# Poke_2_3.net
KiCad netlist of a schematic drawn in EAGLE
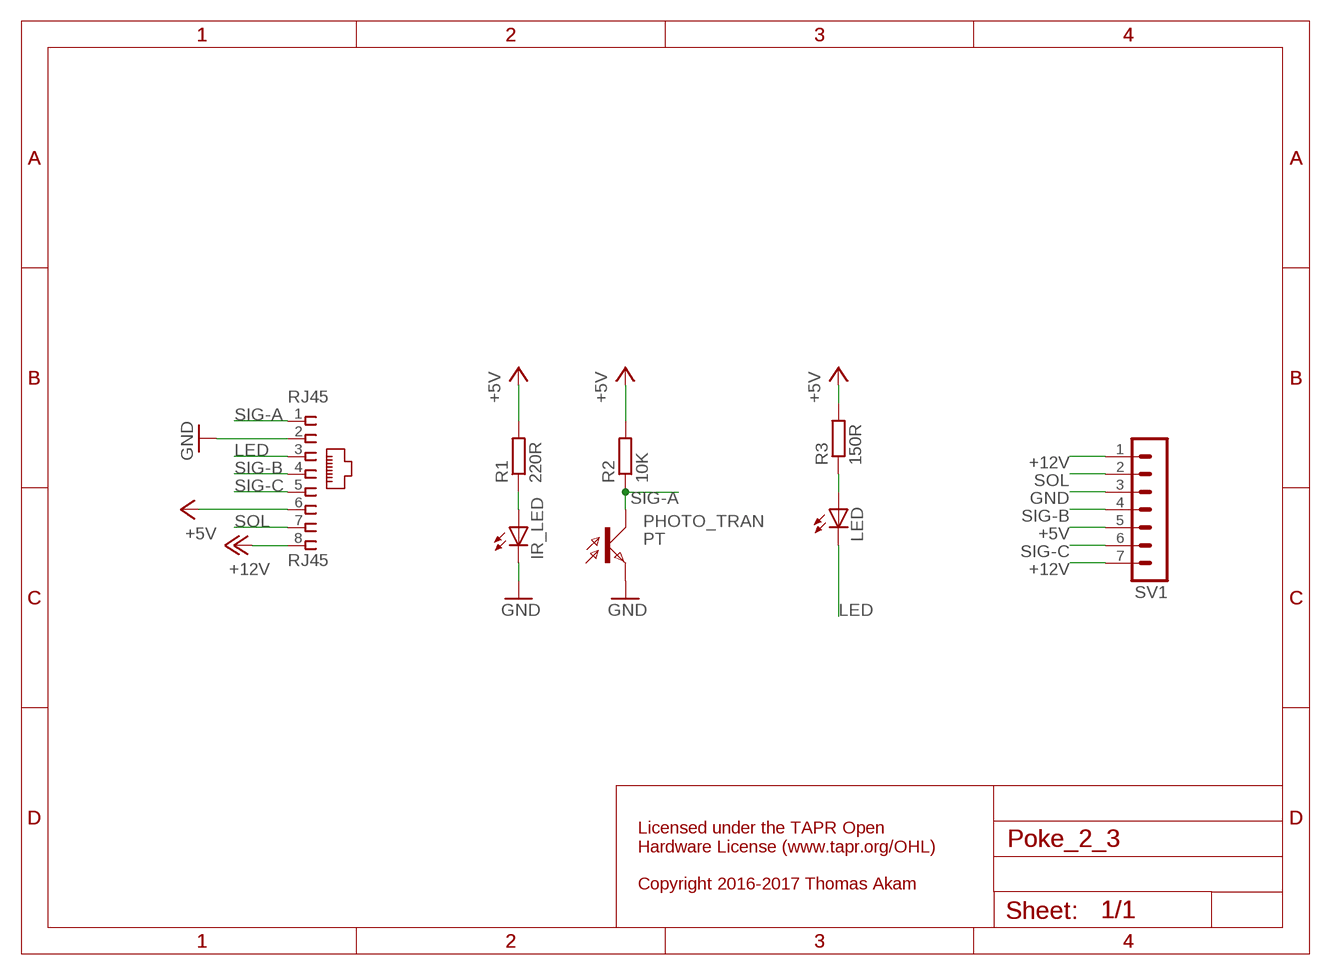
[diagram p0: schematic, sheet 1]

(export (version "E")
  (design (tool "Eeschema 10.0.6"))
  (components
    (comp (ref "IR_LED")
      (value "LEDIRL80A")
      (footprint "eagle-import:IRL80A")
      (libsource (lib "eagle-import") (part "LEDIRL80A"))
    )
    (comp (ref "LED")
      (value "LEDSML0805")
      (footprint "eagle-import:SML0805")
      (libsource (lib "eagle-import") (part "LEDSML0805"))
    )
    (comp (ref "PHOTO_TRAN")
      (value "PT")
      (footprint "eagle-import:LPT80A")
      (fields (field (name "OC_FARNELL") "unknown") (field (name "OC_NEWARK") "unknown"))
      (libsource (lib "eagle-import") (part "LPT80A"))
    )
    (comp (ref "R1")
      (value "220R")
      (footprint "eagle-import:R0805")
      (libsource (lib "eagle-import") (part "R-EU_R0805"))
    )
    (comp (ref "R2")
      (value "10K")
      (footprint "eagle-import:M0805")
      (libsource (lib "eagle-import") (part "R-EU_M0805"))
    )
    (comp (ref "R3")
      (value "150R")
      (footprint "eagle-import:M0805")
      (libsource (lib "eagle-import") (part "R-EU_M0805"))
    )
    (comp (ref "RJ45")
      (value "RJ45")
      (footprint "eagle-import:RJ45-NO-SHIELD-VERTICAL")
      (libsource (lib "eagle-import") (part "RJ45VERTICAL"))
    )
    (comp (ref "SV1")
      (value "MA07-1")
      (footprint "eagle-import:MA07-1")
      (libsource (lib "eagle-import") (part "MA07-1"))
    )
  )
  (nets
    (net (code "1") (name "+5V") (class "Default")
      (node (ref "R1") (pin "2") (pinfunction "2_2") (pintype "passive"))
      (node (ref "R2") (pin "2") (pinfunction "2_2") (pintype "passive"))
      (node (ref "R3") (pin "2") (pinfunction "2_2") (pintype "passive"))
      (node (ref "RJ45") (pin "6") (pinfunction "6_6") (pintype "passive"))
      (node (ref "SV1") (pin "5") (pinfunction "5_5") (pintype "passive"))
    )
    (net (code "2") (name "+12V") (class "Default")
      (node (ref "RJ45") (pin "8") (pinfunction "8_8") (pintype "passive"))
      (node (ref "SV1") (pin "1") (pinfunction "1_1") (pintype "passive"))
      (node (ref "SV1") (pin "7") (pinfunction "7_7") (pintype "passive"))
    )
    (net (code "3") (name "/LED") (class "Default")
      (node (ref "LED") (pin "C") (pinfunction "C_C") (pintype "passive"))
      (node (ref "RJ45") (pin "3") (pinfunction "3_3") (pintype "passive"))
    )
    (net (code "4") (name "/SIG-A") (class "Default")
      (node (ref "PHOTO_TRAN") (pin "C") (pinfunction "C_C") (pintype "passive"))
      (node (ref "R2") (pin "1") (pinfunction "1_1") (pintype "passive"))
      (node (ref "RJ45") (pin "1") (pinfunction "1_1") (pintype "passive"))
    )
    (net (code "5") (name "/SIG-B") (class "Default")
      (node (ref "RJ45") (pin "4") (pinfunction "4_4") (pintype "passive"))
      (node (ref "SV1") (pin "4") (pinfunction "4_4") (pintype "passive"))
    )
    (net (code "6") (name "/SIG-C") (class "Default")
      (node (ref "RJ45") (pin "5") (pinfunction "5_5") (pintype "passive"))
      (node (ref "SV1") (pin "6") (pinfunction "6_6") (pintype "passive"))
    )
    (net (code "7") (name "/SOL") (class "Default")
      (node (ref "RJ45") (pin "7") (pinfunction "7_7") (pintype "passive"))
      (node (ref "SV1") (pin "2") (pinfunction "2_2") (pintype "passive"))
    )
    (net (code "8") (name "GND") (class "Default")
      (node (ref "IR_LED") (pin "K") (pinfunction "C_K") (pintype "passive"))
      (node (ref "PHOTO_TRAN") (pin "E") (pinfunction "E_E") (pintype "passive"))
      (node (ref "RJ45") (pin "2") (pinfunction "2_2") (pintype "passive"))
      (node (ref "SV1") (pin "3") (pinfunction "3_3") (pintype "passive"))
    )
    (net (code "9") (name "Net-(IR_LED-PadA)") (class "Default")
      (node (ref "IR_LED") (pin "A") (pinfunction "A_A") (pintype "passive"))
      (node (ref "R1") (pin "1") (pinfunction "1_1") (pintype "passive"))
    )
    (net (code "10") (name "Net-(LED-PadA)") (class "Default")
      (node (ref "LED") (pin "A") (pinfunction "A_A") (pintype "passive"))
      (node (ref "R3") (pin "1") (pinfunction "1_1") (pintype "passive"))
    )
  )
)
